# Power.net
KiCad netlist of a schematic drawn in Altium Designer
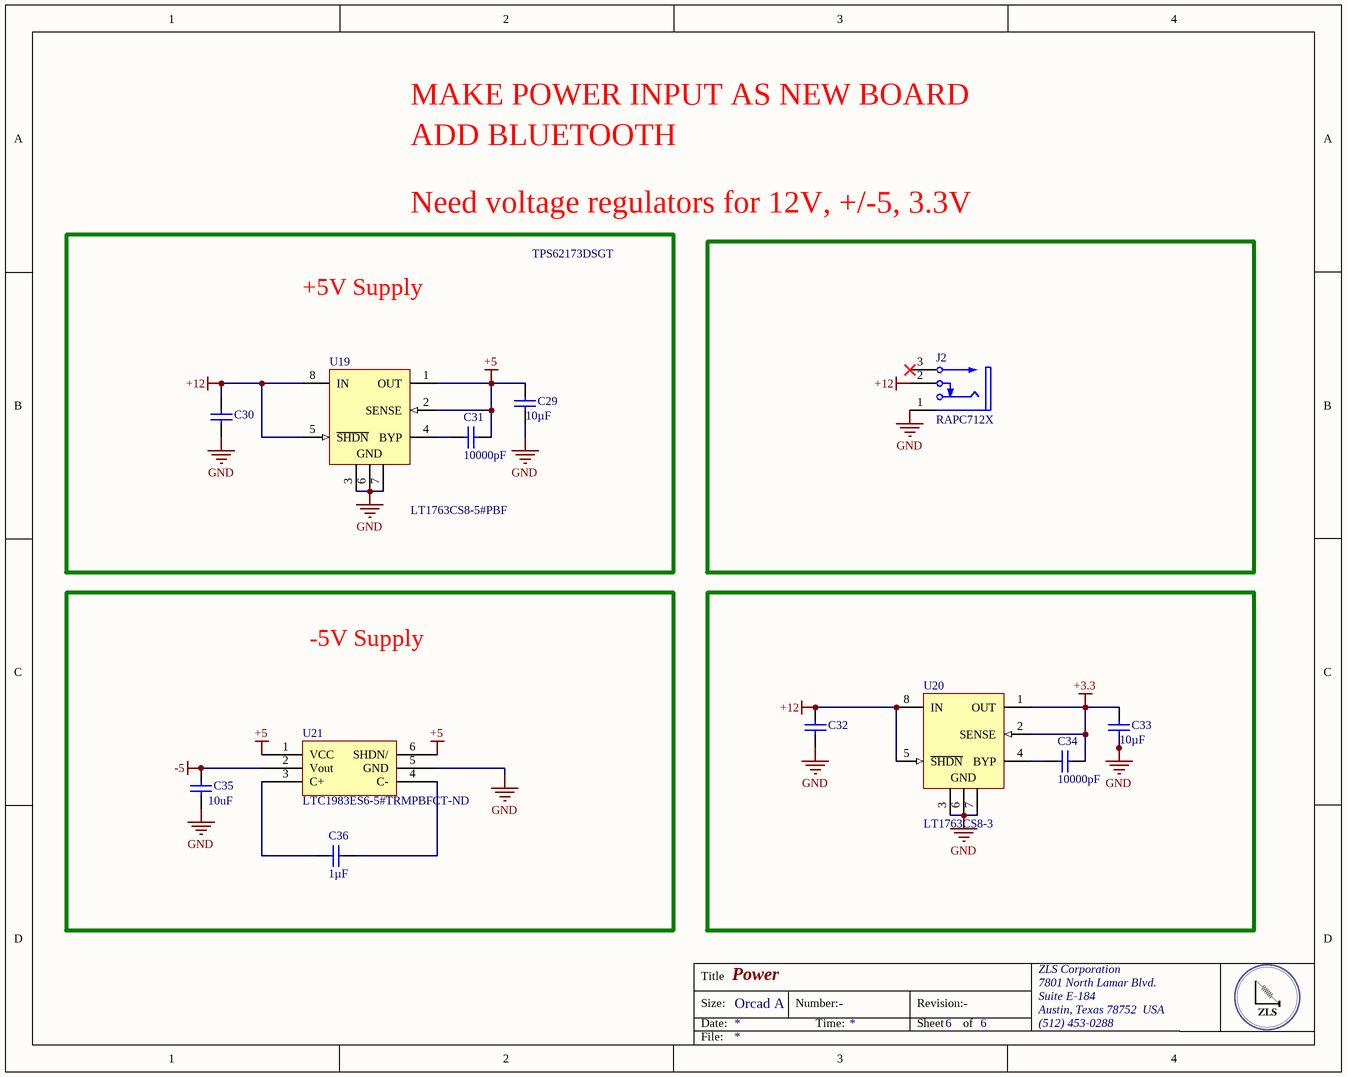
[diagram p0: Power.SchDoc]

(export (version "E")
  (design (tool "Eeschema 10.0.6"))
  (components
    (comp (ref "C29")
      (value "CAP CER 1UF 50V X7R 1210")
      (footprint "CAPC1206(3216)130_N")
      (fields
        (field (name "MANUFACTURER") "Murata Electronics North America")
        (field (name "MANUFACTURER PART NUMBER") "GRM32RR71H105KA01L")
        (field (name "CAPACITANCE") "10µF")
        (field (name "TOLERANCE") "±10%")
      )
      (libsource (lib "Altium Content Vault") (part "CMP-1037-04913-1"))
    )
    (comp (ref "C30")
      (value "1uF")
      (footprint "CAPC1206(3216)130_N")
      (libsource (lib "Altium Content Vault") (part "CMP-1037-04913-1"))
    )
    (comp (ref "C31")
      (value "CAP CER 1UF 50V X7R 1210")
      (footprint "CAPC1206(3216)130_N")
      (fields
        (field (name "MANUFACTURER") "Murata Electronics North America")
        (field (name "MANUFACTURER PART NUMBER") "GRM32RR71H105KA01L")
        (field (name "CAPACITANCE") "10000pF")
        (field (name "TOLERANCE") "±10%")
      )
      (libsource (lib "Altium Content Vault") (part "CMP-1037-04913-1"))
    )
    (comp (ref "C32")
      (value "1uF")
      (footprint "CAPC1206(3216)130_N")
      (libsource (lib "Altium Content Vault") (part "CMP-1037-04913-1"))
    )
    (comp (ref "C33")
      (value "CAP CER 1UF 50V X7R 1210")
      (footprint "CAPC1206(3216)130_N")
      (fields
        (field (name "MANUFACTURER") "Murata Electronics North America")
        (field (name "MANUFACTURER PART NUMBER") "GRM32RR71H105KA01L")
        (field (name "CAPACITANCE") "10µF")
        (field (name "TOLERANCE") "±10%")
      )
      (libsource (lib "Altium Content Vault") (part "CMP-1037-04913-1"))
    )
    (comp (ref "C34")
      (value "CAP CER 1UF 50V X7R 1210")
      (footprint "CAPC1206(3216)130_N")
      (fields
        (field (name "MANUFACTURER") "Murata Electronics North America")
        (field (name "MANUFACTURER PART NUMBER") "GRM32RR71H105KA01L")
        (field (name "CAPACITANCE") "10000pF")
        (field (name "TOLERANCE") "±10%")
      )
      (libsource (lib "Altium Content Vault") (part "CMP-1037-04913-1"))
    )
    (comp (ref "C35")
      (value "CAP CER 10UF 6.3V X5R 1206")
      (footprint "CAPC1206(3216)130_N")
      (fields
        (field (name "MANUFACTURER") "Taiyo Yuden")
        (field (name "MANUFACTURER PART NUMBER") "JMK316BJ106ML-T")
        (field (name "TOLERANCE") "±20%")
        (field (name "CAPACITANCE") "10uF")
      )
      (libsource (lib "Altium Content Vault") (part "CMP-1037-04913-1"))
    )
    (comp (ref "C36")
      (value "CAP CER 1UF 10V X5R 0805")
      (footprint "CAPC1206(3216)130_N")
      (fields
        (field (name "CAPACITANCE") "1µF")
        (field (name "MANUFACTURER") "Taiyo Yuden")
        (field (name "MANUFACTURER PART NUMBER") "LMK212BJ105MD-T")
        (field (name "TOLERANCE") "±20%")
      )
      (libsource (lib "Altium Content Vault") (part "CMP-1037-04913-1"))
    )
    (comp (ref "J2")
      (value "RAPC712X")
      (footprint "SWITCH-RAPC712X-3_V")
      (description "Conn Powerjack Mini R/A PCMT, 5 A, 3-Pin THD, RoHS")
      (fields (field (name "MANUFACTURER") "Switchcraft"))
      (libsource (lib "Altium Content Vault") (part "SWITCH-RAPC712X-3"))
    )
    (comp (ref "U19")
      (value "LT1763CS8-5#PBF")
      (footprint "LT-S8-8_M")
      (fields (field (name "MANUFACTURER") "Linear Technology"))
      (libsource (lib "Altium Content Vault") (part "LT-LT1763-S8-8"))
    )
    (comp (ref "U20")
      (value "LT1763CS8-3")
      (footprint "LT-S8-8_L")
      (fields (field (name "MANUFACTURER") "Linear Technology"))
      (libsource (lib "Altium Content Vault") (part "LT-LT1763-S8-8"))
    )
    (comp (ref "U21")
      (value "LTC1983ES6-5#TRMPBF")
      (footprint "SOT95P323X100-6N")
      (fields
        (field (name "SUPPLIER PART NUMBER 1") "LTC1983ES6-5#TRMPBFCT-ND")
        (field (name "MANUFACTURER") "Linear Technology/Analog Devices")
        (field (name "BASE PART NUMBER") "LTC1983-5")
      )
      (libsource (lib "ZLS_Schematic_lib") (part "LTC1983ES6-5#TRMPBF"))
    )
  )
  (nets
    (net (code "1") (name "+3.3") (class "Default")
      (node (ref "C33") (pin "2") (pinfunction "2_2") (pintype "passive"))
      (node (ref "C34") (pin "1") (pinfunction "1_1") (pintype "passive"))
      (node (ref "U20") (pin "1") (pinfunction "OUT_1") (pintype "power_in"))
      (node (ref "U20") (pin "2") (pinfunction "SENSE_2") (pintype "input"))
    )
    (net (code "2") (name "+5") (class "Default")
      (node (ref "C29") (pin "2") (pinfunction "2_2") (pintype "passive"))
      (node (ref "C31") (pin "1") (pinfunction "1_1") (pintype "passive"))
      (node (ref "U19") (pin "1") (pinfunction "OUT_1") (pintype "power_in"))
      (node (ref "U19") (pin "2") (pinfunction "SENSE_2") (pintype "input"))
      (node (ref "U21") (pin "1") (pinfunction "VCC_1") (pintype "passive"))
      (node (ref "U21") (pin "6") (pinfunction "SHDN/_6") (pintype "passive"))
    )
    (net (code "3") (name "+12") (class "Default")
      (node (ref "C30") (pin "2") (pinfunction "2_2") (pintype "passive"))
      (node (ref "C32") (pin "2") (pinfunction "2_2") (pintype "passive"))
      (node (ref "J2") (pin "2") (pinfunction "2_2") (pintype "passive"))
      (node (ref "U19") (pin "5") (pinfunction "~{SHDN}_5") (pintype "input"))
      (node (ref "U19") (pin "8") (pinfunction "IN_8") (pintype "power_in"))
      (node (ref "U20") (pin "5") (pinfunction "~{SHDN}_5") (pintype "input"))
      (node (ref "U20") (pin "8") (pinfunction "IN_8") (pintype "power_in"))
    )
    (net (code "4") (name "-5") (class "Default")
      (node (ref "C35") (pin "2") (pinfunction "2_2") (pintype "passive"))
      (node (ref "U21") (pin "2") (pinfunction "Vout_2") (pintype "passive"))
    )
    (net (code "5") (name "GND") (class "Default")
      (node (ref "C29") (pin "1") (pinfunction "1_1") (pintype "passive"))
      (node (ref "C30") (pin "1") (pinfunction "1_1") (pintype "passive"))
      (node (ref "C32") (pin "1") (pinfunction "1_1") (pintype "passive"))
      (node (ref "C33") (pin "1") (pinfunction "1_1") (pintype "passive"))
      (node (ref "C35") (pin "1") (pinfunction "1_1") (pintype "passive"))
      (node (ref "J2") (pin "1") (pinfunction "1_1") (pintype "passive"))
      (node (ref "U19") (pin "3") (pinfunction "GND_3") (pintype "power_in"))
      (node (ref "U19") (pin "6") (pinfunction "GND_6") (pintype "power_in"))
      (node (ref "U19") (pin "7") (pinfunction "GND_7") (pintype "power_in"))
      (node (ref "U20") (pin "3") (pinfunction "GND_3") (pintype "power_in"))
      (node (ref "U20") (pin "6") (pinfunction "GND_6") (pintype "power_in"))
      (node (ref "U20") (pin "7") (pinfunction "GND_7") (pintype "power_in"))
      (node (ref "U21") (pin "5") (pinfunction "GND_5") (pintype "passive"))
    )
    (net (code "6") (name "Net-(U19-BYP)") (class "Default")
      (node (ref "C31") (pin "2") (pinfunction "2_2") (pintype "passive"))
      (node (ref "U19") (pin "4") (pinfunction "BYP_4") (pintype "passive"))
    )
    (net (code "7") (name "Net-(U20-BYP)") (class "Default")
      (node (ref "C34") (pin "2") (pinfunction "2_2") (pintype "passive"))
      (node (ref "U20") (pin "4") (pinfunction "BYP_4") (pintype "passive"))
    )
    (net (code "8") (name "Net-(U21-C+)") (class "Default")
      (node (ref "C36") (pin "2") (pinfunction "2_2") (pintype "passive"))
      (node (ref "U21") (pin "3") (pinfunction "C+_3") (pintype "passive"))
    )
    (net (code "9") (name "Net-(U21-C-)") (class "Default")
      (node (ref "C36") (pin "1") (pinfunction "1_1") (pintype "passive"))
      (node (ref "U21") (pin "4") (pinfunction "C-_4") (pintype "passive"))
    )
    (net (code "10") (name "unconnected-(J2-Pad3)") (class "Default")
      (node (ref "J2") (pin "3") (pinfunction "3_3") (pintype "passive+no_connect"))
    )
  )
)
